# TickTagREV3.net
KiCad netlist of a schematic drawn in EAGLE
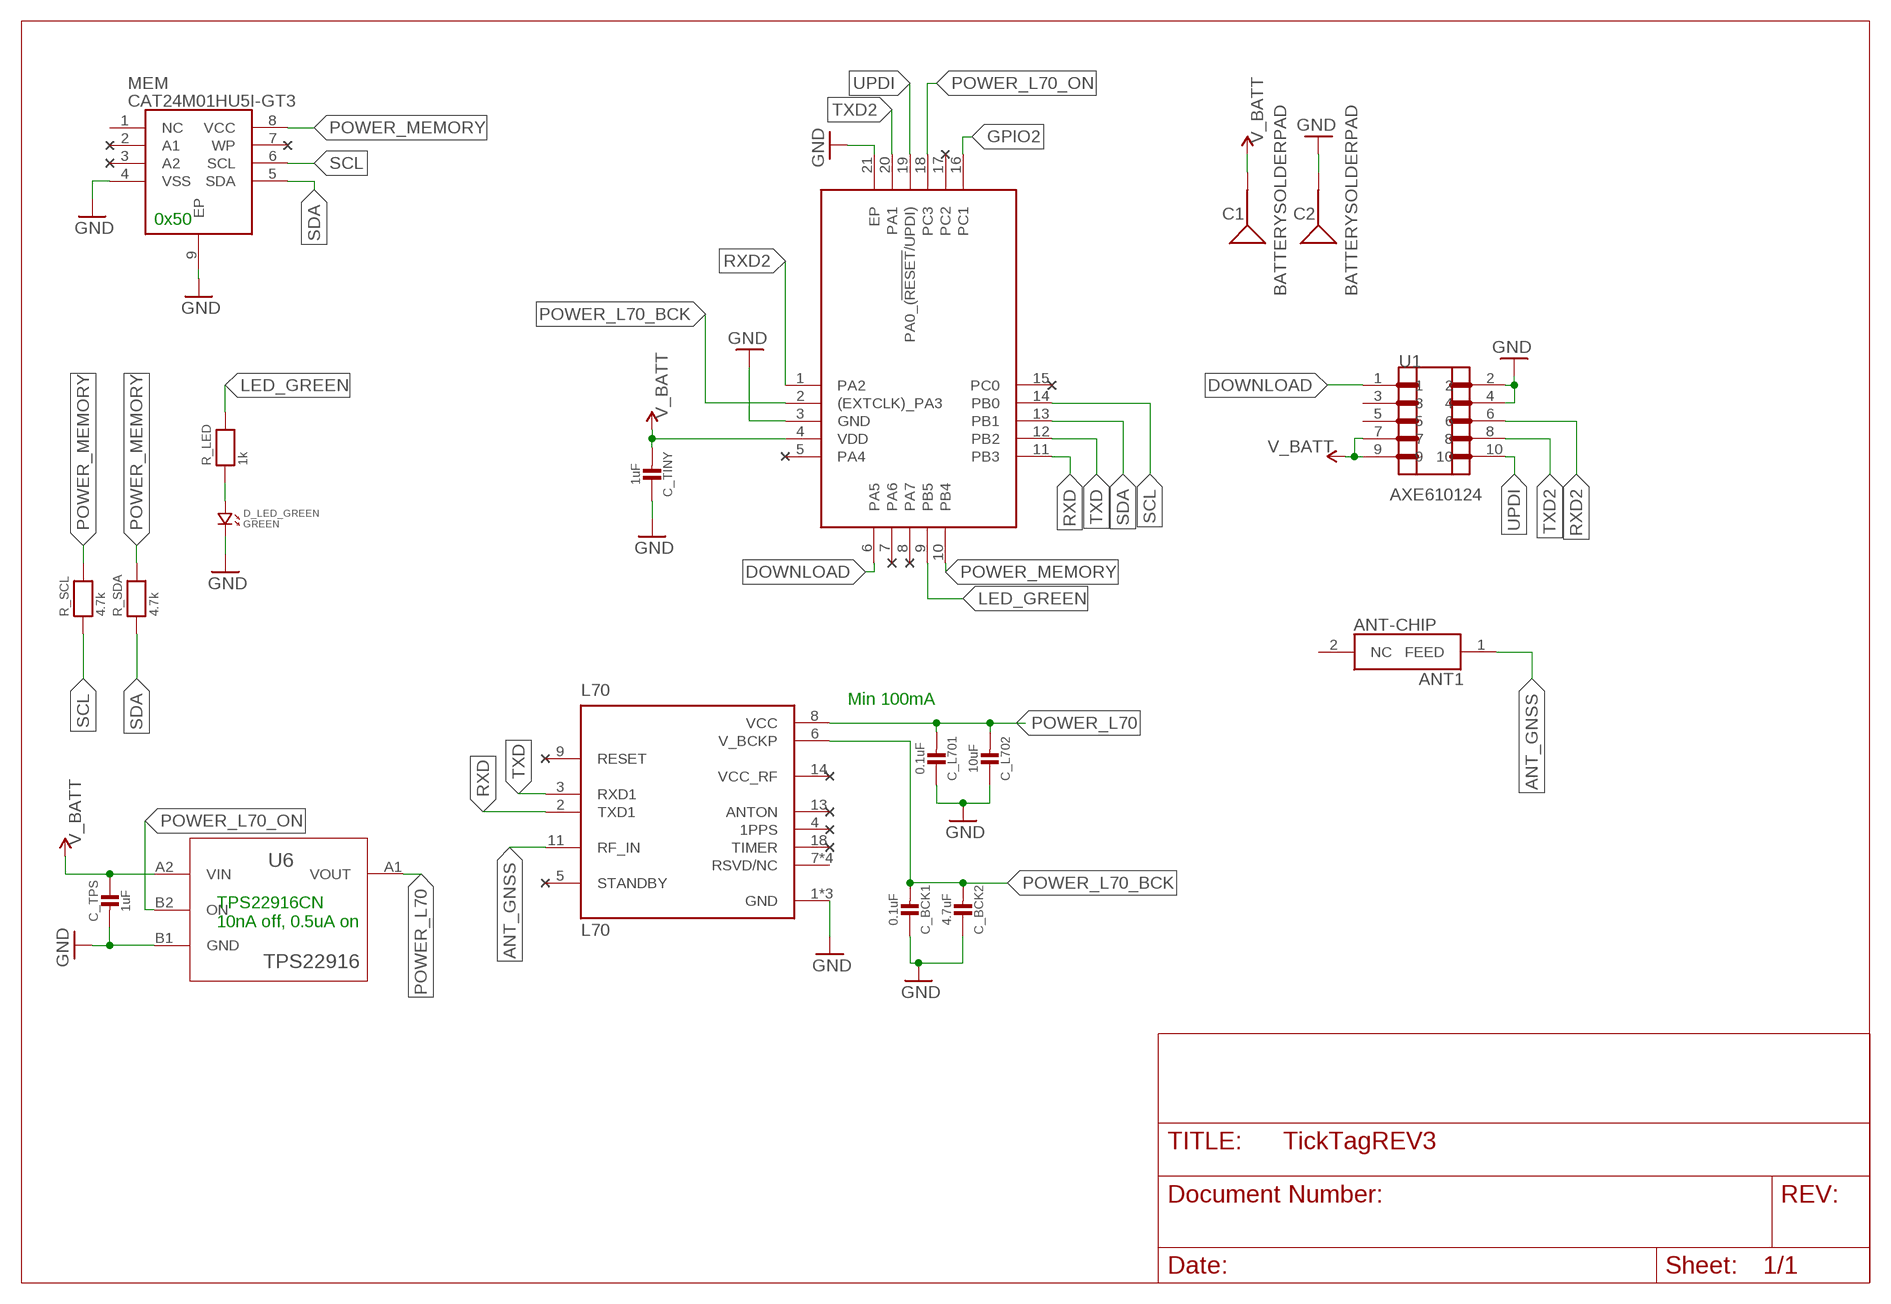
[diagram p0: schematic, sheet 1]

(export (version "E")
  (design (tool "Eeschema 10.0.6"))
  (components
    (comp (ref "ANT-CHIP")
      (value "ANT1")
      (footprint "eagle-import:SAMACSYS_PARTS_1575AT43A0040E")
      (fields
        (field (name "MANUFACTURER_PART_NUMBER") "1575AT43A0040E")
        (field (name "MOUSER_PART_NUMBER") "609-1575AT43A0040E")
      )
      (libsource (lib "eagle-import") (part "SAMACSYS_PARTS_1575AT43A0040E"))
    )
    (comp (ref "ATTINY")
      (value "ATTINY1616-MFR")
      (footprint "eagle-import:QFN40P300X300X90-21N")
      (fields
        (field (name "MANUFACTURER_PART_NUMBER") "ATTINY1606-MFR")
        (field (name "MOUSER_PART_NUMBER") "556-ATTINY1606-MFR")
      )
      (libsource (lib "eagle-import") (part "ATTINY1616-MFR"))
    )
    (comp (ref "C1")
      (value "BATTERYSOLDERPAD")
      (footprint "eagle-import:BATTERYSOLDERPAD")
      (libsource (lib "eagle-import") (part "BATTERYSOLDERPAD"))
    )
    (comp (ref "C2")
      (value "BATTERYSOLDERPAD")
      (footprint "eagle-import:BATTERYSOLDERPAD")
      (libsource (lib "eagle-import") (part "BATTERYSOLDERPAD"))
    )
    (comp (ref "C_BCK1")
      (value "0.1uF")
      (footprint "eagle-import:MICROBUILDER__0402MP")
      (libsource (lib "eagle-import") (part "MICROBUILDER_CAP_CERAMIC_0402MP"))
    )
    (comp (ref "C_BCK2")
      (value "4.7uF")
      (footprint "eagle-import:MICROBUILDER__0402MP")
      (libsource (lib "eagle-import") (part "MICROBUILDER_CAP_CERAMIC_0402MP"))
    )
    (comp (ref "C_L701")
      (value "0.1uF")
      (footprint "eagle-import:MICROBUILDER__0402MP")
      (libsource (lib "eagle-import") (part "MICROBUILDER_CAP_CERAMIC_0402MP"))
    )
    (comp (ref "C_L702")
      (value "10uF")
      (footprint "eagle-import:MICROBUILDER__0402MP")
      (libsource (lib "eagle-import") (part "MICROBUILDER_CAP_CERAMIC_0402MP"))
    )
    (comp (ref "C_TINY")
      (value "1uF")
      (footprint "eagle-import:MICROBUILDER__0402MP")
      (libsource (lib "eagle-import") (part "MICROBUILDER_CAP_CERAMIC_0402MP"))
    )
    (comp (ref "C_TPS")
      (value "1uF")
      (footprint "eagle-import:MICROBUILDER__0402MP")
      (libsource (lib "eagle-import") (part "MICROBUILDER_CAP_CERAMIC_0402MP"))
    )
    (comp (ref "D_LED_GREEN")
      (value "GREEN")
      (footprint "eagle-import:CMONR_STANDARDPARTS_0402.LED")
      (libsource (lib "eagle-import") (part "CMONR_STANDARDPARTS_LED.0402"))
    )
    (comp (ref "L70")
      (value "L70")
      (footprint "eagle-import:XCVR_L70")
      (fields (field (name "MF") "Quectel"))
      (libsource (lib "eagle-import") (part "L70"))
    )
    (comp (ref "MEM")
      (value "CAT24M01HU5I-GT3")
      (footprint "eagle-import:SON50P300X200X55-9N")
      (fields
        (field (name "MOUSER_PART_NUMBER") "863-CAT24M01HU5I-GT3")
        (field (name "RS_PART_NUMBER") "7814831P")
      )
      (libsource (lib "eagle-import") (part "CAT24M01HU5I-GT3"))
    )
    (comp (ref "R_LED")
      (value "1k")
      (footprint "eagle-import:MICROBUILDER__0402MP")
      (libsource (lib "eagle-import") (part "MICROBUILDER_RESISTOR_0402MP"))
    )
    (comp (ref "R_SCL")
      (value "4.7k")
      (footprint "eagle-import:MICROBUILDER__0402MP")
      (libsource (lib "eagle-import") (part "MICROBUILDER_RESISTOR_0402MP"))
    )
    (comp (ref "R_SDA")
      (value "4.7k")
      (footprint "eagle-import:MICROBUILDER__0402MP")
      (libsource (lib "eagle-import") (part "MICROBUILDER_RESISTOR_0402MP"))
    )
    (comp (ref "U1")
      (value "AXE610124")
      (footprint "eagle-import:AXE610124")
      (libsource (lib "eagle-import") (part "AXE610124"))
    )
    (comp (ref "U6")
      (value "TPS22916")
      (footprint "eagle-import:TPS22916")
      (fields (field (name "MF") "Texas Instruments") (field (name "MP") "LP5900TL-3.0"))
      (libsource (lib "eagle-import") (part "TPS22916"))
    )
  )
  (nets
    (net (code "1") (name "ANT_GNSS") (class "Default")
      (node (ref "ANT-CHIP") (pin "1") (pinfunction "FEED_1") (pintype "input"))
      (node (ref "L70") (pin "11") (pinfunction "RF_IN_11") (pintype "input"))
    )
    (net (code "2") (name "DOWNLOAD") (class "Default")
      (node (ref "ATTINY") (pin "6") (pinfunction "PA5_6") (pintype "bidirectional"))
      (node (ref "U1") (pin "1") (pinfunction "1_1") (pintype "passive"))
    )
    (net (code "3") (name "GND") (class "Default")
      (node (ref "ATTINY") (pin "21") (pinfunction "EP_21") (pintype "bidirectional"))
      (node (ref "ATTINY") (pin "3") (pinfunction "GND_3") (pintype "bidirectional"))
      (node (ref "C2") (pin "1") (pinfunction "SIGNAL_1") (pintype "bidirectional"))
      (node (ref "C_BCK1") (pin "1") (pinfunction "1_1") (pintype "passive"))
      (node (ref "C_BCK2") (pin "1") (pinfunction "1_1") (pintype "passive"))
      (node (ref "C_L701") (pin "1") (pinfunction "1_1") (pintype "passive"))
      (node (ref "C_L702") (pin "1") (pinfunction "1_1") (pintype "passive"))
      (node (ref "C_TINY") (pin "1") (pinfunction "1_1") (pintype "passive"))
      (node (ref "C_TPS") (pin "2") (pinfunction "2_2") (pintype "passive"))
      (node (ref "D_LED_GREEN") (pin "P$2") (pinfunction "2_P$2") (pintype "bidirectional"))
      (node (ref "L70") (pin "1") (pinfunction "GND_1") (pintype "power_in"))
      (node (ref "L70") (pin "10") (pinfunction "GND_10") (pintype "power_in"))
      (node (ref "L70") (pin "12") (pinfunction "GND_12") (pintype "power_in"))
      (node (ref "MEM") (pin "4") (pinfunction "VSS_4") (pintype "power_in"))
      (node (ref "MEM") (pin "9") (pinfunction "EP_9") (pintype "bidirectional"))
      (node (ref "U1") (pin "2") (pinfunction "2_2") (pintype "passive"))
      (node (ref "U1") (pin "4") (pinfunction "4_4") (pintype "passive"))
      (node (ref "U6") (pin "B1") (pinfunction "GND_B1") (pintype "passive"))
    )
    (net (code "4") (name "GPIO2") (class "Default")
      (node (ref "ATTINY") (pin "16") (pinfunction "PC1_16") (pintype "bidirectional"))
    )
    (net (code "5") (name "LED_GREEN") (class "Default")
      (node (ref "ATTINY") (pin "9") (pinfunction "PB5_9") (pintype "bidirectional"))
      (node (ref "R_LED") (pin "2") (pinfunction "2_2") (pintype "passive"))
    )
    (net (code "6") (name "Net-(D_LED_GREEN-1)") (class "Default")
      (node (ref "D_LED_GREEN") (pin "P$1") (pinfunction "1_P$1") (pintype "bidirectional"))
      (node (ref "R_LED") (pin "1") (pinfunction "1_1") (pintype "passive"))
    )
    (net (code "7") (name "POWER_L70") (class "Default")
      (node (ref "C_L701") (pin "2") (pinfunction "2_2") (pintype "passive"))
      (node (ref "C_L702") (pin "2") (pinfunction "2_2") (pintype "passive"))
      (node (ref "L70") (pin "8") (pinfunction "VCC_8") (pintype "power_in"))
      (node (ref "U6") (pin "A1") (pinfunction "VOUT_A1") (pintype "output"))
    )
    (net (code "8") (name "POWER_L70_BCK") (class "Default")
      (node (ref "ATTINY") (pin "2") (pinfunction "(EXTCLK)_PA3_2") (pintype "bidirectional"))
      (node (ref "C_BCK1") (pin "2") (pinfunction "2_2") (pintype "passive"))
      (node (ref "C_BCK2") (pin "2") (pinfunction "2_2") (pintype "passive"))
      (node (ref "L70") (pin "6") (pinfunction "V_BCKP_6") (pintype "power_in"))
    )
    (net (code "9") (name "POWER_L70_ON") (class "Default")
      (node (ref "ATTINY") (pin "18") (pinfunction "PC3_18") (pintype "bidirectional"))
      (node (ref "U6") (pin "B2") (pinfunction "ON_B2") (pintype "input"))
    )
    (net (code "10") (name "POWER_MEMORY") (class "Default")
      (node (ref "ATTINY") (pin "10") (pinfunction "PB4_10") (pintype "bidirectional"))
      (node (ref "MEM") (pin "8") (pinfunction "VCC_8") (pintype "power_in"))
      (node (ref "R_SCL") (pin "2") (pinfunction "2_2") (pintype "passive"))
      (node (ref "R_SDA") (pin "2") (pinfunction "2_2") (pintype "passive"))
    )
    (net (code "11") (name "RXD") (class "Default")
      (node (ref "ATTINY") (pin "11") (pinfunction "PB3_11") (pintype "bidirectional"))
      (node (ref "L70") (pin "2") (pinfunction "TXD1_2") (pintype "output"))
    )
    (net (code "12") (name "RXD2") (class "Default")
      (node (ref "ATTINY") (pin "1") (pinfunction "PA2_1") (pintype "bidirectional"))
      (node (ref "U1") (pin "6") (pinfunction "6_6") (pintype "passive"))
    )
    (net (code "13") (name "SCL") (class "Default")
      (node (ref "ATTINY") (pin "14") (pinfunction "PB0_14") (pintype "bidirectional"))
      (node (ref "MEM") (pin "6") (pinfunction "SCL_6") (pintype "bidirectional"))
      (node (ref "R_SCL") (pin "1") (pinfunction "1_1") (pintype "passive"))
    )
    (net (code "14") (name "SDA") (class "Default")
      (node (ref "ATTINY") (pin "13") (pinfunction "PB1_13") (pintype "bidirectional"))
      (node (ref "MEM") (pin "5") (pinfunction "SDA_5") (pintype "bidirectional"))
      (node (ref "R_SDA") (pin "1") (pinfunction "1_1") (pintype "passive"))
    )
    (net (code "15") (name "TXD") (class "Default")
      (node (ref "ATTINY") (pin "12") (pinfunction "PB2_12") (pintype "bidirectional"))
      (node (ref "L70") (pin "3") (pinfunction "RXD1_3") (pintype "input"))
    )
    (net (code "16") (name "TXD2") (class "Default")
      (node (ref "ATTINY") (pin "20") (pinfunction "PA1_20") (pintype "bidirectional"))
      (node (ref "U1") (pin "8") (pinfunction "8_8") (pintype "passive"))
    )
    (net (code "17") (name "UPDI") (class "Default")
      (node (ref "ATTINY") (pin "19") (pinfunction "PA0_(~{RESET}/UPDI)_19") (pintype "bidirectional"))
      (node (ref "U1") (pin "10") (pinfunction "10_10") (pintype "passive"))
    )
    (net (code "18") (name "V_BATT") (class "Default")
      (node (ref "ATTINY") (pin "4") (pinfunction "VDD_4") (pintype "bidirectional"))
      (node (ref "C1") (pin "1") (pinfunction "SIGNAL_1") (pintype "bidirectional"))
      (node (ref "C_TINY") (pin "2") (pinfunction "2_2") (pintype "passive"))
      (node (ref "C_TPS") (pin "1") (pinfunction "1_1") (pintype "passive"))
      (node (ref "U1") (pin "7") (pinfunction "7_7") (pintype "passive"))
      (node (ref "U1") (pin "9") (pinfunction "9_9") (pintype "passive"))
      (node (ref "U6") (pin "A2") (pinfunction "VIN_A2") (pintype "power_in"))
    )
    (net (code "19") (name "unconnected-(ANT-CHIP-NC-Pad2)") (class "Default")
      (node (ref "ANT-CHIP") (pin "2") (pinfunction "NC_2") (pintype "no_connect"))
    )
    (net (code "20") (name "unconnected-(ATTINY-PA4-Pad5)") (class "Default")
      (node (ref "ATTINY") (pin "5") (pinfunction "PA4_5") (pintype "bidirectional"))
    )
    (net (code "21") (name "unconnected-(ATTINY-PA6-Pad7)") (class "Default")
      (node (ref "ATTINY") (pin "7") (pinfunction "PA6_7") (pintype "bidirectional"))
    )
    (net (code "22") (name "unconnected-(ATTINY-PA7-Pad8)") (class "Default")
      (node (ref "ATTINY") (pin "8") (pinfunction "PA7_8") (pintype "bidirectional"))
    )
    (net (code "23") (name "unconnected-(ATTINY-PC0-Pad15)") (class "Default")
      (node (ref "ATTINY") (pin "15") (pinfunction "PC0_15") (pintype "bidirectional"))
    )
    (net (code "24") (name "unconnected-(ATTINY-PC2-Pad17)") (class "Default")
      (node (ref "ATTINY") (pin "17") (pinfunction "PC2_17") (pintype "bidirectional"))
    )
    (net (code "25") (name "unconnected-(L70-1PPS-Pad4)") (class "Default")
      (node (ref "L70") (pin "4") (pinfunction "1PPS_4") (pintype "output"))
    )
    (net (code "26") (name "unconnected-(L70-ANTON-Pad13)") (class "Default")
      (node (ref "L70") (pin "13") (pinfunction "ANTON_13") (pintype "output"))
    )
    (net (code "27") (name "unconnected-(L70-RESET-Pad9)") (class "Default")
      (node (ref "L70") (pin "9") (pinfunction "RESET_9") (pintype "input"))
    )
    (net (code "28") (name "unconnected-(L70-RSVD{slash}NC-Pad7)") (class "Default")
      (node (ref "L70") (pin "7") (pinfunction "RSVD/NC_7") (pintype "no_connect"))
    )
    (net (code "29") (name "unconnected-(L70-RSVD{slash}NC-Pad15)") (class "Default")
      (node (ref "L70") (pin "15") (pinfunction "RSVD/NC_15") (pintype "no_connect"))
    )
    (net (code "30") (name "unconnected-(L70-RSVD{slash}NC-Pad16)") (class "Default")
      (node (ref "L70") (pin "16") (pinfunction "RSVD/NC_16") (pintype "no_connect"))
    )
    (net (code "31") (name "unconnected-(L70-RSVD{slash}NC-Pad17)") (class "Default")
      (node (ref "L70") (pin "17") (pinfunction "RSVD/NC_17") (pintype "no_connect"))
    )
    (net (code "32") (name "unconnected-(L70-STANDBY-Pad5)") (class "Default")
      (node (ref "L70") (pin "5") (pinfunction "STANDBY_5") (pintype "input"))
    )
    (net (code "33") (name "unconnected-(L70-TIMER-Pad18)") (class "Default")
      (node (ref "L70") (pin "18") (pinfunction "TIMER_18") (pintype "output"))
    )
    (net (code "34") (name "unconnected-(L70-VCC_RF-Pad14)") (class "Default")
      (node (ref "L70") (pin "14") (pinfunction "VCC_RF_14") (pintype "output"))
    )
    (net (code "35") (name "unconnected-(MEM-A1-Pad2)") (class "Default")
      (node (ref "MEM") (pin "2") (pinfunction "A1_2") (pintype "bidirectional"))
    )
    (net (code "36") (name "unconnected-(MEM-A2-Pad3)") (class "Default")
      (node (ref "MEM") (pin "3") (pinfunction "A2_3") (pintype "bidirectional"))
    )
    (net (code "37") (name "unconnected-(MEM-NC-Pad1)") (class "Default")
      (node (ref "MEM") (pin "1") (pinfunction "NC_1") (pintype "no_connect"))
    )
    (net (code "38") (name "unconnected-(MEM-WP-Pad7)") (class "Default")
      (node (ref "MEM") (pin "7") (pinfunction "WP_7") (pintype "bidirectional"))
    )
    (net (code "39") (name "unconnected-(U1-Pad3)") (class "Default")
      (node (ref "U1") (pin "3") (pinfunction "3_3") (pintype "passive"))
    )
    (net (code "40") (name "unconnected-(U1-Pad5)") (class "Default")
      (node (ref "U1") (pin "5") (pinfunction "5_5") (pintype "passive"))
    )
  )
)
